# iv-12-tube-board-v2.net
KiCad netlist of a schematic drawn in EAGLE
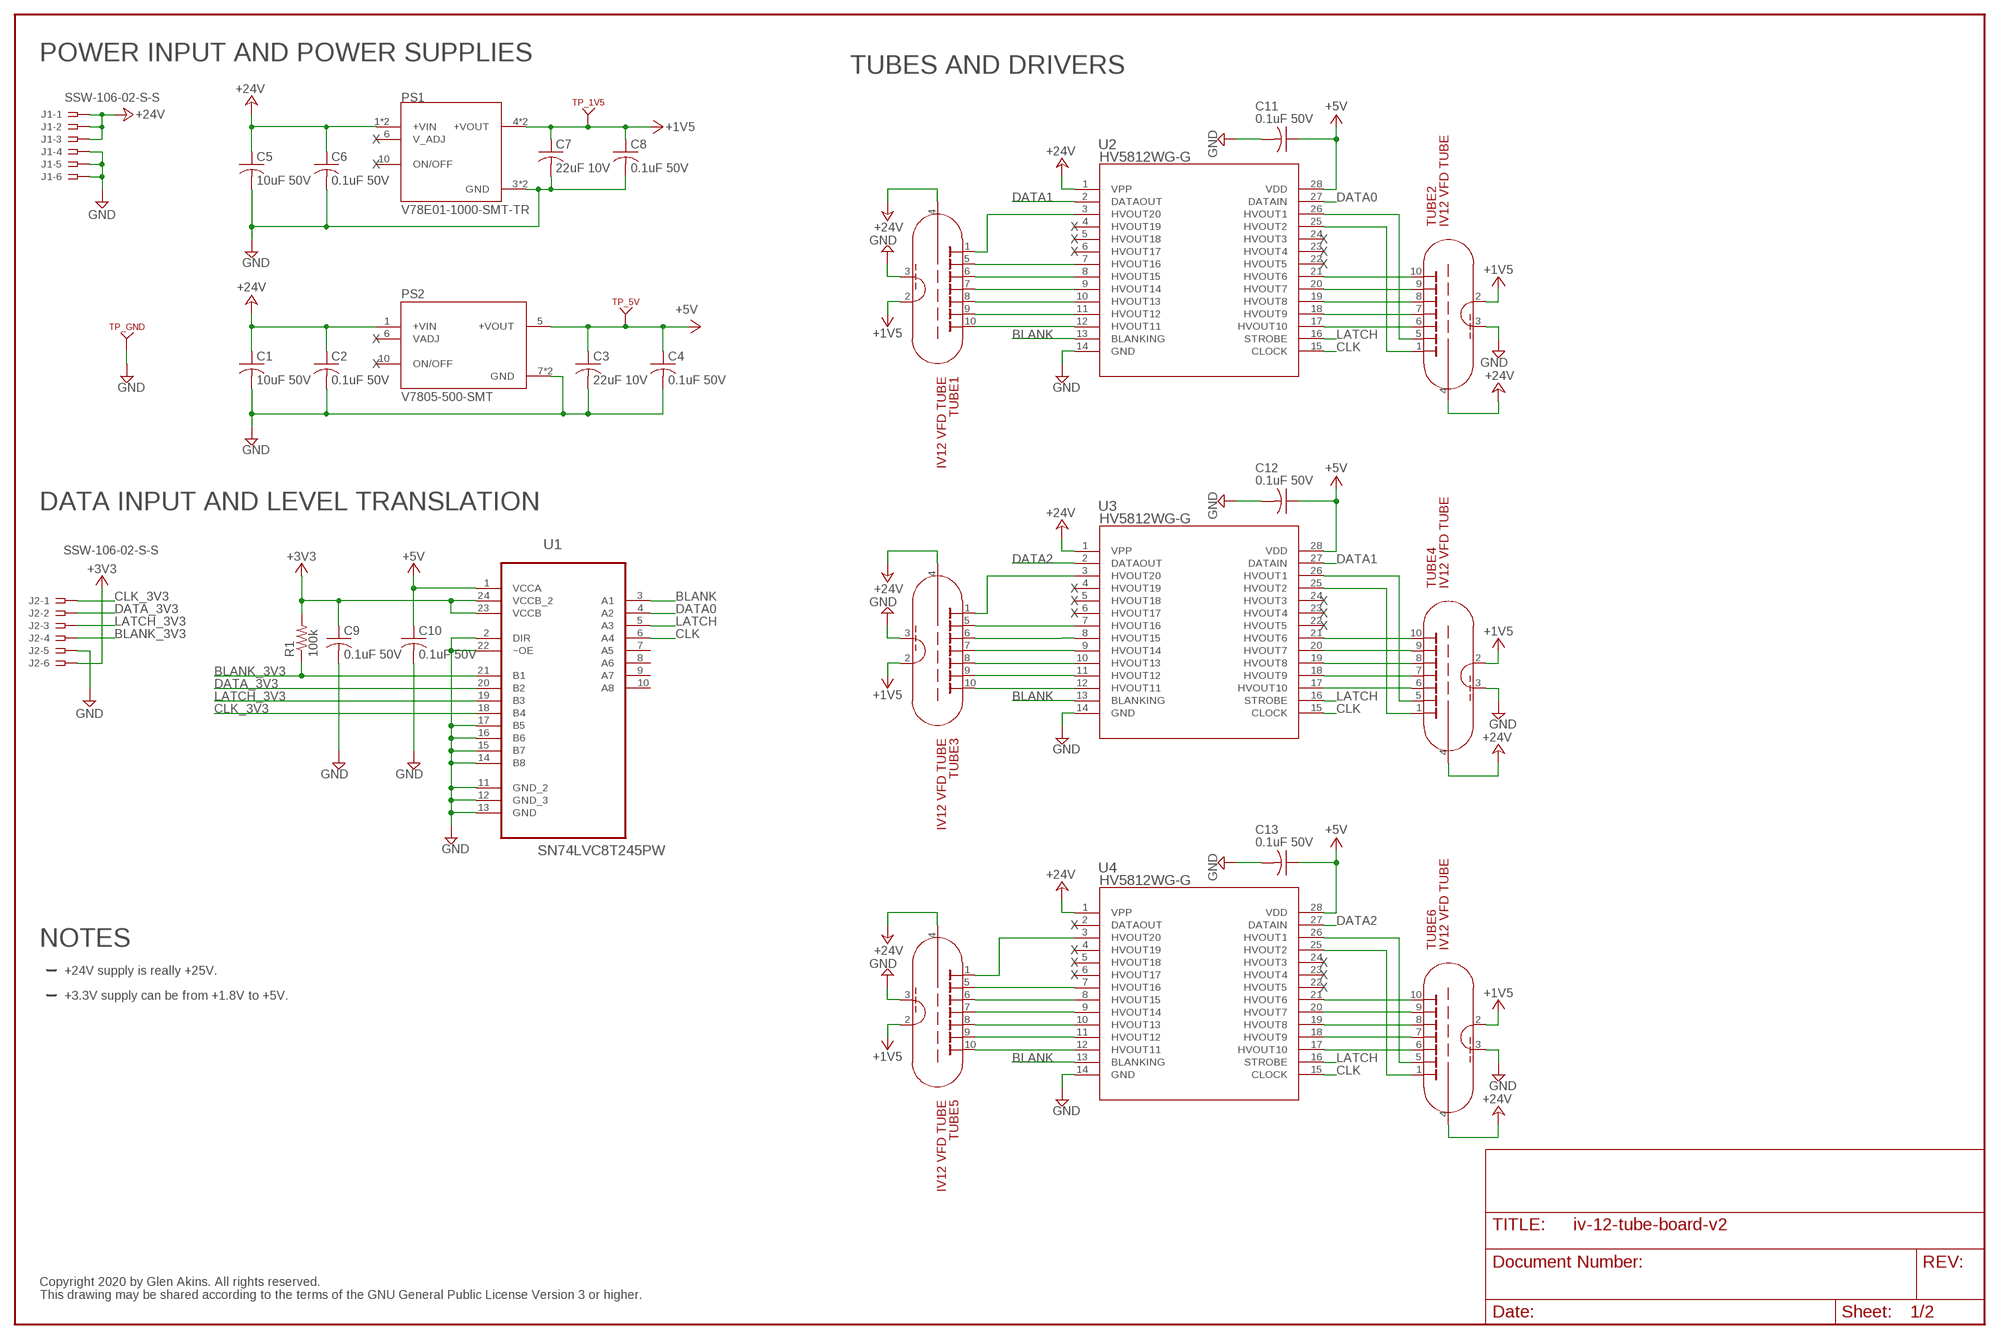
[diagram p0: schematic, sheet 1]
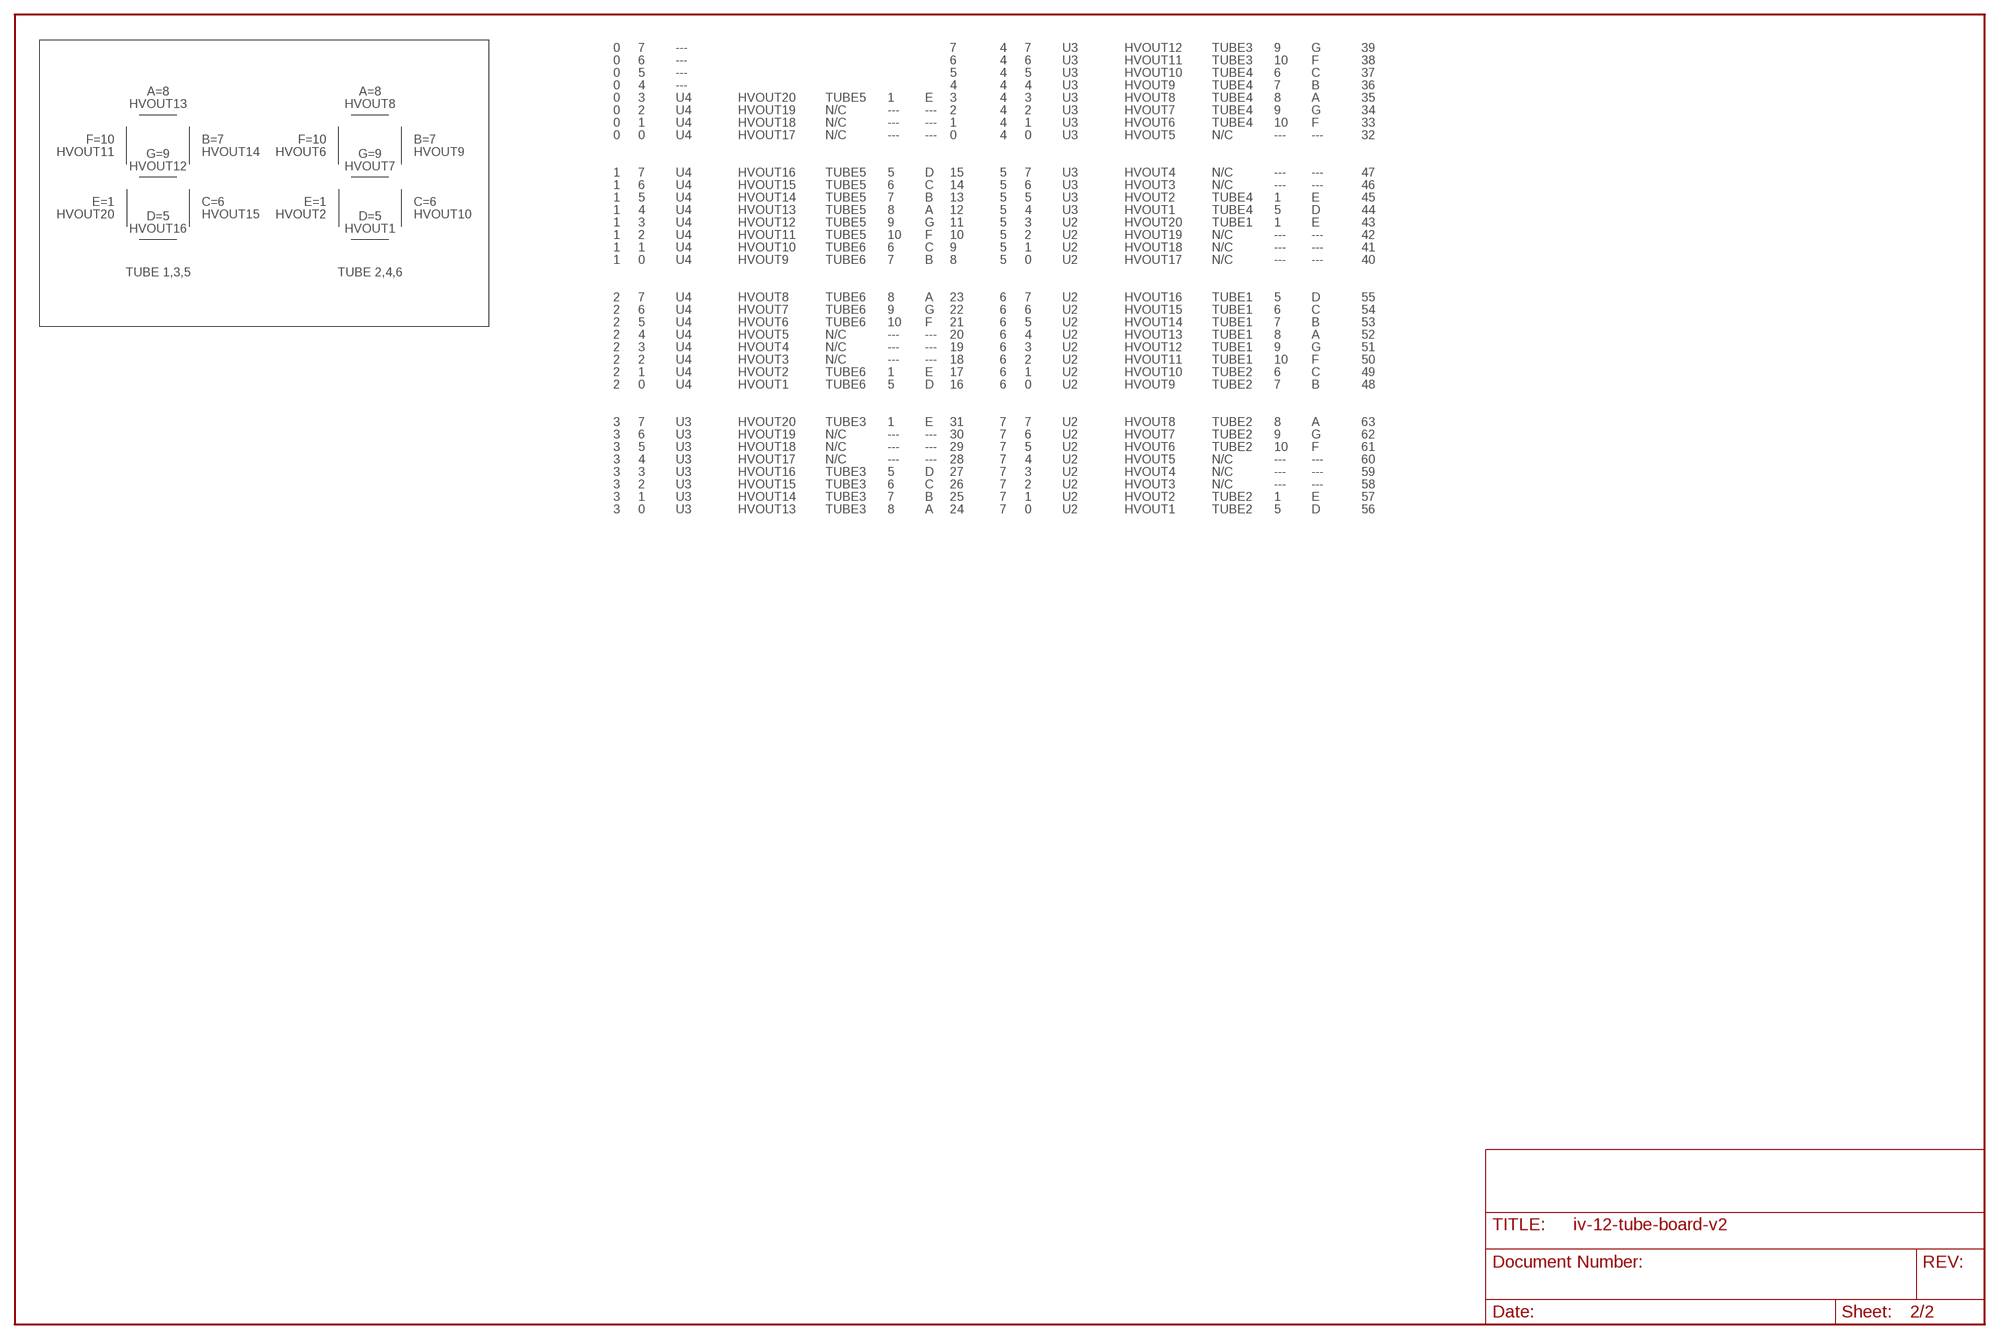
[diagram p1: schematic, sheet 2]

(export (version "E")
  (design (tool "Eeschema 10.0.6"))
  (components
    (comp (ref "C1")
      (value "10uF 50V")
      (footprint "eagle-import:C1210K")
      (fields (field (name "MFR") "KEMET") (field (name "MFR_PART_NO") "C1210C106K5RACTU"))
      (libsource (lib "eagle-import") (part "C-USC1210K"))
    )
    (comp (ref "C2")
      (value "0.1uF 50V")
      (footprint "eagle-import:C1206K")
      (fields (field (name "MFR") "KEMET") (field (name "MFR_PART_NO") "C1206S104M5RACTU"))
      (libsource (lib "eagle-import") (part "C-USC1206K"))
    )
    (comp (ref "C3")
      (value "22uF 10V")
      (footprint "eagle-import:C1206K")
      (fields (field (name "MFR") "KEMET") (field (name "MFR_PART_NO") "C1206C226K8RAC7800"))
      (libsource (lib "eagle-import") (part "C-USC1206K"))
    )
    (comp (ref "C4")
      (value "0.1uF 50V")
      (footprint "eagle-import:C1206K")
      (fields (field (name "MFR") "KEMET") (field (name "MFR_PART_NO") "C1206S104M5RACTU"))
      (libsource (lib "eagle-import") (part "C-USC1206K"))
    )
    (comp (ref "C5")
      (value "10uF 50V")
      (footprint "eagle-import:C1210K")
      (fields (field (name "MFR") "KEMET") (field (name "MFR_PART_NO") "C1210C106K5RACTU"))
      (libsource (lib "eagle-import") (part "C-USC1210K"))
    )
    (comp (ref "C6")
      (value "0.1uF 50V")
      (footprint "eagle-import:C1206K")
      (fields (field (name "MFR") "KEMET") (field (name "MFR_PART_NO") "C1206S104M5RACTU"))
      (libsource (lib "eagle-import") (part "C-USC1206K"))
    )
    (comp (ref "C7")
      (value "22uF 10V")
      (footprint "eagle-import:C1206K")
      (fields (field (name "MFR") "KEMET") (field (name "MFR_PART_NO") "C1206C226K8RAC7800"))
      (libsource (lib "eagle-import") (part "C-USC1206K"))
    )
    (comp (ref "C8")
      (value "0.1uF 50V")
      (footprint "eagle-import:C1206K")
      (fields (field (name "MFR") "KEMET") (field (name "MFR_PART_NO") "C1206S104M5RACTU"))
      (libsource (lib "eagle-import") (part "C-USC1206K"))
    )
    (comp (ref "C9")
      (value "0.1uF 50V")
      (footprint "eagle-import:C0805K")
      (libsource (lib "eagle-import") (part "C-USC0805K"))
    )
    (comp (ref "C10")
      (value "0.1uF 50V")
      (footprint "eagle-import:C0805K")
      (libsource (lib "eagle-import") (part "C-USC0805K"))
    )
    (comp (ref "C11")
      (value "0.1uF 50V")
      (footprint "eagle-import:C0805")
      (libsource (lib "eagle-import") (part "C-USC0805"))
    )
    (comp (ref "C12")
      (value "0.1uF 50V")
      (footprint "eagle-import:C0805")
      (libsource (lib "eagle-import") (part "C-USC0805"))
    )
    (comp (ref "C13")
      (value "0.1uF 50V")
      (footprint "eagle-import:C0805")
      (libsource (lib "eagle-import") (part "C-USC0805"))
    )
    (comp (ref "J1")
      (value "SSW-106-02-S-S")
      (footprint "eagle-import:SSW-106-02-S-S")
      (libsource (lib "eagle-import") (part "SSW-106-02-S-S"))
    )
    (comp (ref "J2")
      (value "SSW-106-02-S-S")
      (footprint "eagle-import:SSW-106-02-S-S")
      (libsource (lib "eagle-import") (part "SSW-106-02-S-S"))
    )
    (comp (ref "PS1")
      (value "V78E01-1000-SMT-TR")
      (footprint "eagle-import:CONV_V78E01-1000-SMT-TR")
      (fields (field (name "DIGI-KEY_PART_NUMBER") "102-5030-1-ND") (field (name "MF") "CUI Inc."))
      (libsource (lib "eagle-import") (part "V78E01-1000-SMT-TR"))
    )
    (comp (ref "PS2")
      (value "V7805-500-SMT")
      (footprint "eagle-import:CONV_V7805-500-SMT")
      (fields (field (name "MANUFACTURER") "CUI Inc"))
      (libsource (lib "eagle-import") (part "V7805-500-SMT"))
    )
    (comp (ref "R1")
      (value "100k")
      (footprint "eagle-import:R0805")
      (libsource (lib "eagle-import") (part "R-US_R0805"))
    )
    (comp (ref "TP_1V5")
      (value "KEYSTONE_500X")
      (footprint "eagle-import:KEYSTONE_TP500X")
      (libsource (lib "eagle-import") (part "KEYSTONE_500X"))
    )
    (comp (ref "TP_5V")
      (value "KEYSTONE_500X")
      (footprint "eagle-import:KEYSTONE_TP500X")
      (libsource (lib "eagle-import") (part "KEYSTONE_500X"))
    )
    (comp (ref "TP_GND")
      (value "KEYSTONE_500X")
      (footprint "eagle-import:KEYSTONE_TP500X")
      (libsource (lib "eagle-import") (part "KEYSTONE_500X"))
    )
    (comp (ref "TUBE1")
      (value "IV12 VFD TUBE")
      (footprint "eagle-import:IV-12-VFD-TUBE-11.9MM-10PIN-34DEG")
      (libsource (lib "eagle-import") (part "IV-12-VFD-TUBE"))
    )
    (comp (ref "TUBE2")
      (value "IV12 VFD TUBE")
      (footprint "eagle-import:IV-12-VFD-TUBE-11.9MM-10PIN-34DEG")
      (libsource (lib "eagle-import") (part "IV-12-VFD-TUBE"))
    )
    (comp (ref "TUBE3")
      (value "IV12 VFD TUBE")
      (footprint "eagle-import:IV-12-VFD-TUBE-11.9MM-10PIN-34DEG")
      (libsource (lib "eagle-import") (part "IV-12-VFD-TUBE"))
    )
    (comp (ref "TUBE4")
      (value "IV12 VFD TUBE")
      (footprint "eagle-import:IV-12-VFD-TUBE-11.9MM-10PIN-34DEG")
      (libsource (lib "eagle-import") (part "IV-12-VFD-TUBE"))
    )
    (comp (ref "TUBE5")
      (value "IV12 VFD TUBE")
      (footprint "eagle-import:IV-12-VFD-TUBE-11.9MM-10PIN-34DEG")
      (libsource (lib "eagle-import") (part "IV-12-VFD-TUBE"))
    )
    (comp (ref "TUBE6")
      (value "IV12 VFD TUBE")
      (footprint "eagle-import:IV-12-VFD-TUBE-11.9MM-10PIN-34DEG")
      (libsource (lib "eagle-import") (part "IV-12-VFD-TUBE"))
    )
    (comp (ref "U1")
      (value "SN74LVC8T245PW")
      (footprint "eagle-import:SOP65P640X120-24N")
      (fields (field (name "MPN") "SN74AVC8T245PW"))
      (libsource (lib "eagle-import") (part "SN74AVC8T245PW"))
    )
    (comp (ref "U2")
      (value "HV5812WG-G")
      (footprint "eagle-import:SOW28_17P90X7P50")
      (fields (field (name "COPYRIGHT") "Copyright (C) 2018 Accelerated Designs. All rights reserved"))
      (libsource (lib "eagle-import") (part "HV5812WG-G"))
    )
    (comp (ref "U3")
      (value "HV5812WG-G")
      (footprint "eagle-import:SOW28_17P90X7P50")
      (fields (field (name "COPYRIGHT") "Copyright (C) 2018 Accelerated Designs. All rights reserved"))
      (libsource (lib "eagle-import") (part "HV5812WG-G"))
    )
    (comp (ref "U4")
      (value "HV5812WG-G")
      (footprint "eagle-import:SOW28_17P90X7P50")
      (fields (field (name "COPYRIGHT") "Copyright (C) 2018 Accelerated Designs. All rights reserved"))
      (libsource (lib "eagle-import") (part "HV5812WG-G"))
    )
  )
  (nets
    (net (code "1") (name "+1V5") (class "Default")
      (node (ref "C7") (pin "1") (pinfunction "1_1") (pintype "passive"))
      (node (ref "C8") (pin "1") (pinfunction "1_1") (pintype "passive"))
      (node (ref "PS1") (pin "4") (pinfunction "+VOUT_4") (pintype "output"))
      (node (ref "PS1") (pin "5") (pinfunction "+VOUT_5") (pintype "output"))
      (node (ref "TP_1V5") (pin "1") (pinfunction "P$1_1") (pintype "bidirectional"))
      (node (ref "TUBE1") (pin "2") (pinfunction "2_2") (pintype "bidirectional"))
      (node (ref "TUBE2") (pin "2") (pinfunction "2_2") (pintype "bidirectional"))
      (node (ref "TUBE3") (pin "2") (pinfunction "2_2") (pintype "bidirectional"))
      (node (ref "TUBE4") (pin "2") (pinfunction "2_2") (pintype "bidirectional"))
      (node (ref "TUBE5") (pin "2") (pinfunction "2_2") (pintype "bidirectional"))
      (node (ref "TUBE6") (pin "2") (pinfunction "2_2") (pintype "bidirectional"))
    )
    (net (code "2") (name "+3V3") (class "Default")
      (node (ref "C9") (pin "1") (pinfunction "1_1") (pintype "passive"))
      (node (ref "J2") (pin "6") (pinfunction "1_6") (pintype "passive"))
      (node (ref "R1") (pin "2") (pinfunction "2_2") (pintype "passive"))
      (node (ref "U1") (pin "23") (pinfunction "VCCB_23") (pintype "power_in"))
      (node (ref "U1") (pin "24") (pinfunction "VCCB_2_24") (pintype "power_in"))
    )
    (net (code "3") (name "+5V") (class "Default")
      (node (ref "C10") (pin "1") (pinfunction "1_1") (pintype "passive"))
      (node (ref "C11") (pin "1") (pinfunction "1_1") (pintype "passive"))
      (node (ref "C12") (pin "1") (pinfunction "1_1") (pintype "passive"))
      (node (ref "C13") (pin "1") (pinfunction "1_1") (pintype "passive"))
      (node (ref "C3") (pin "1") (pinfunction "1_1") (pintype "passive"))
      (node (ref "C4") (pin "1") (pinfunction "1_1") (pintype "passive"))
      (node (ref "PS2") (pin "5") (pinfunction "+VOUT_5") (pintype "output"))
      (node (ref "TP_5V") (pin "1") (pinfunction "P$1_1") (pintype "bidirectional"))
      (node (ref "U1") (pin "1") (pinfunction "VCCA_1") (pintype "power_in"))
      (node (ref "U2") (pin "28") (pinfunction "VDD_28") (pintype "power_in"))
      (node (ref "U3") (pin "28") (pinfunction "VDD_28") (pintype "power_in"))
      (node (ref "U4") (pin "28") (pinfunction "VDD_28") (pintype "power_in"))
    )
    (net (code "4") (name "+24V") (class "Default")
      (node (ref "C1") (pin "1") (pinfunction "1_1") (pintype "passive"))
      (node (ref "C2") (pin "1") (pinfunction "1_1") (pintype "passive"))
      (node (ref "C5") (pin "1") (pinfunction "1_1") (pintype "passive"))
      (node (ref "C6") (pin "1") (pinfunction "1_1") (pintype "passive"))
      (node (ref "J1") (pin "1") (pinfunction "1_1") (pintype "passive"))
      (node (ref "J1") (pin "2") (pinfunction "1_2") (pintype "passive"))
      (node (ref "J1") (pin "3") (pinfunction "1_3") (pintype "passive"))
      (node (ref "PS1") (pin "1") (pinfunction "+VIN_1") (pintype "input"))
      (node (ref "PS1") (pin "2") (pinfunction "+VIN_2") (pintype "input"))
      (node (ref "PS2") (pin "1") (pinfunction "+VIN_1") (pintype "input"))
      (node (ref "TUBE1") (pin "4") (pinfunction "4_4") (pintype "bidirectional"))
      (node (ref "TUBE2") (pin "4") (pinfunction "4_4") (pintype "bidirectional"))
      (node (ref "TUBE3") (pin "4") (pinfunction "4_4") (pintype "bidirectional"))
      (node (ref "TUBE4") (pin "4") (pinfunction "4_4") (pintype "bidirectional"))
      (node (ref "TUBE5") (pin "4") (pinfunction "4_4") (pintype "bidirectional"))
      (node (ref "TUBE6") (pin "4") (pinfunction "4_4") (pintype "bidirectional"))
      (node (ref "U2") (pin "1") (pinfunction "VPP_1") (pintype "power_in"))
      (node (ref "U3") (pin "1") (pinfunction "VPP_1") (pintype "power_in"))
      (node (ref "U4") (pin "1") (pinfunction "VPP_1") (pintype "power_in"))
    )
    (net (code "5") (name "BLANK") (class "Default")
      (node (ref "U1") (pin "3") (pinfunction "A1_3") (pintype "bidirectional"))
      (node (ref "U2") (pin "13") (pinfunction "BLANKING_13") (pintype "passive"))
      (node (ref "U3") (pin "13") (pinfunction "BLANKING_13") (pintype "passive"))
      (node (ref "U4") (pin "13") (pinfunction "BLANKING_13") (pintype "passive"))
    )
    (net (code "6") (name "BLANK_3V3") (class "Default")
      (node (ref "J2") (pin "4") (pinfunction "1_4") (pintype "passive"))
      (node (ref "R1") (pin "1") (pinfunction "1_1") (pintype "passive"))
      (node (ref "U1") (pin "21") (pinfunction "B1_21") (pintype "bidirectional"))
    )
    (net (code "7") (name "CLK") (class "Default")
      (node (ref "U1") (pin "6") (pinfunction "A4_6") (pintype "bidirectional"))
      (node (ref "U2") (pin "15") (pinfunction "CLOCK_15") (pintype "passive"))
      (node (ref "U3") (pin "15") (pinfunction "CLOCK_15") (pintype "passive"))
      (node (ref "U4") (pin "15") (pinfunction "CLOCK_15") (pintype "passive"))
    )
    (net (code "8") (name "CLK_3V3") (class "Default")
      (node (ref "J2") (pin "1") (pinfunction "1_1") (pintype "passive"))
      (node (ref "U1") (pin "18") (pinfunction "B4_18") (pintype "bidirectional"))
    )
    (net (code "9") (name "DATA0") (class "Default")
      (node (ref "U1") (pin "4") (pinfunction "A2_4") (pintype "bidirectional"))
      (node (ref "U2") (pin "27") (pinfunction "DATAIN_27") (pintype "input"))
    )
    (net (code "10") (name "DATA1") (class "Default")
      (node (ref "U2") (pin "2") (pinfunction "DATAOUT_2") (pintype "output"))
      (node (ref "U3") (pin "27") (pinfunction "DATAIN_27") (pintype "input"))
    )
    (net (code "11") (name "DATA2") (class "Default")
      (node (ref "U3") (pin "2") (pinfunction "DATAOUT_2") (pintype "output"))
      (node (ref "U4") (pin "27") (pinfunction "DATAIN_27") (pintype "input"))
    )
    (net (code "12") (name "DATA_3V3") (class "Default")
      (node (ref "J2") (pin "2") (pinfunction "1_2") (pintype "passive"))
      (node (ref "U1") (pin "20") (pinfunction "B2_20") (pintype "bidirectional"))
    )
    (net (code "13") (name "GND") (class "Default")
      (node (ref "C1") (pin "2") (pinfunction "2_2") (pintype "passive"))
      (node (ref "C10") (pin "2") (pinfunction "2_2") (pintype "passive"))
      (node (ref "C11") (pin "2") (pinfunction "2_2") (pintype "passive"))
      (node (ref "C12") (pin "2") (pinfunction "2_2") (pintype "passive"))
      (node (ref "C13") (pin "2") (pinfunction "2_2") (pintype "passive"))
      (node (ref "C2") (pin "2") (pinfunction "2_2") (pintype "passive"))
      (node (ref "C3") (pin "2") (pinfunction "2_2") (pintype "passive"))
      (node (ref "C4") (pin "2") (pinfunction "2_2") (pintype "passive"))
      (node (ref "C5") (pin "2") (pinfunction "2_2") (pintype "passive"))
      (node (ref "C6") (pin "2") (pinfunction "2_2") (pintype "passive"))
      (node (ref "C7") (pin "2") (pinfunction "2_2") (pintype "passive"))
      (node (ref "C8") (pin "2") (pinfunction "2_2") (pintype "passive"))
      (node (ref "C9") (pin "2") (pinfunction "2_2") (pintype "passive"))
      (node (ref "J1") (pin "4") (pinfunction "1_4") (pintype "passive"))
      (node (ref "J1") (pin "5") (pinfunction "1_5") (pintype "passive"))
      (node (ref "J1") (pin "6") (pinfunction "1_6") (pintype "passive"))
      (node (ref "J2") (pin "5") (pinfunction "1_5") (pintype "passive"))
      (node (ref "PS1") (pin "3") (pinfunction "GND_3") (pintype "power_in"))
      (node (ref "PS1") (pin "7") (pinfunction "GND_7") (pintype "power_in"))
      (node (ref "PS2") (pin "7") (pinfunction "GND_7") (pintype "power_in"))
      (node (ref "PS2") (pin "9") (pinfunction "GND_9") (pintype "power_in"))
      (node (ref "TP_GND") (pin "1") (pinfunction "P$1_1") (pintype "bidirectional"))
      (node (ref "TUBE1") (pin "3") (pinfunction "3_3") (pintype "bidirectional"))
      (node (ref "TUBE2") (pin "3") (pinfunction "3_3") (pintype "bidirectional"))
      (node (ref "TUBE3") (pin "3") (pinfunction "3_3") (pintype "bidirectional"))
      (node (ref "TUBE4") (pin "3") (pinfunction "3_3") (pintype "bidirectional"))
      (node (ref "TUBE5") (pin "3") (pinfunction "3_3") (pintype "bidirectional"))
      (node (ref "TUBE6") (pin "3") (pinfunction "3_3") (pintype "bidirectional"))
      (node (ref "U1") (pin "11") (pinfunction "GND_2_11") (pintype "passive"))
      (node (ref "U1") (pin "12") (pinfunction "GND_3_12") (pintype "passive"))
      (node (ref "U1") (pin "13") (pinfunction "GND_13") (pintype "passive"))
      (node (ref "U1") (pin "14") (pinfunction "B8_14") (pintype "bidirectional"))
      (node (ref "U1") (pin "15") (pinfunction "B7_15") (pintype "bidirectional"))
      (node (ref "U1") (pin "16") (pinfunction "B6_16") (pintype "bidirectional"))
      (node (ref "U1") (pin "17") (pinfunction "B5_17") (pintype "bidirectional"))
      (node (ref "U1") (pin "2") (pinfunction "DIR_2") (pintype "input"))
      (node (ref "U1") (pin "22") (pinfunction "~{OE}_22") (pintype "input"))
      (node (ref "U2") (pin "14") (pinfunction "GND_14") (pintype "passive"))
      (node (ref "U3") (pin "14") (pinfunction "GND_14") (pintype "passive"))
      (node (ref "U4") (pin "14") (pinfunction "GND_14") (pintype "passive"))
    )
    (net (code "14") (name "LATCH") (class "Default")
      (node (ref "U1") (pin "5") (pinfunction "A3_5") (pintype "bidirectional"))
      (node (ref "U2") (pin "16") (pinfunction "STROBE_16") (pintype "passive"))
      (node (ref "U3") (pin "16") (pinfunction "STROBE_16") (pintype "passive"))
      (node (ref "U4") (pin "16") (pinfunction "STROBE_16") (pintype "passive"))
    )
    (net (code "15") (name "LATCH_3V3") (class "Default")
      (node (ref "J2") (pin "3") (pinfunction "1_3") (pintype "passive"))
      (node (ref "U1") (pin "19") (pinfunction "B3_19") (pintype "bidirectional"))
    )
    (net (code "16") (name "Net-(U2-HVOUT1)") (class "Default")
      (node (ref "TUBE2") (pin "5") (pinfunction "5_5") (pintype "bidirectional"))
      (node (ref "U2") (pin "26") (pinfunction "HVOUT1_26") (pintype "output"))
    )
    (net (code "17") (name "Net-(U2-HVOUT2)") (class "Default")
      (node (ref "TUBE2") (pin "1") (pinfunction "1_1") (pintype "bidirectional"))
      (node (ref "U2") (pin "25") (pinfunction "HVOUT2_25") (pintype "output"))
    )
    (net (code "18") (name "Net-(U2-HVOUT6)") (class "Default")
      (node (ref "TUBE2") (pin "10") (pinfunction "10_10") (pintype "bidirectional"))
      (node (ref "U2") (pin "21") (pinfunction "HVOUT6_21") (pintype "output"))
    )
    (net (code "19") (name "Net-(U2-HVOUT7)") (class "Default")
      (node (ref "TUBE2") (pin "9") (pinfunction "9_9") (pintype "bidirectional"))
      (node (ref "U2") (pin "20") (pinfunction "HVOUT7_20") (pintype "output"))
    )
    (net (code "20") (name "Net-(U2-HVOUT8)") (class "Default")
      (node (ref "TUBE2") (pin "8") (pinfunction "8_8") (pintype "bidirectional"))
      (node (ref "U2") (pin "19") (pinfunction "HVOUT8_19") (pintype "output"))
    )
    (net (code "21") (name "Net-(U2-HVOUT9)") (class "Default")
      (node (ref "TUBE2") (pin "7") (pinfunction "7_7") (pintype "bidirectional"))
      (node (ref "U2") (pin "18") (pinfunction "HVOUT9_18") (pintype "output"))
    )
    (net (code "22") (name "Net-(U2-HVOUT10)") (class "Default")
      (node (ref "TUBE2") (pin "6") (pinfunction "6_6") (pintype "bidirectional"))
      (node (ref "U2") (pin "17") (pinfunction "HVOUT10_17") (pintype "output"))
    )
    (net (code "23") (name "Net-(U2-HVOUT11)") (class "Default")
      (node (ref "TUBE1") (pin "10") (pinfunction "10_10") (pintype "bidirectional"))
      (node (ref "U2") (pin "12") (pinfunction "HVOUT11_12") (pintype "output"))
    )
    (net (code "24") (name "Net-(U2-HVOUT12)") (class "Default")
      (node (ref "TUBE1") (pin "9") (pinfunction "9_9") (pintype "bidirectional"))
      (node (ref "U2") (pin "11") (pinfunction "HVOUT12_11") (pintype "output"))
    )
    (net (code "25") (name "Net-(U2-HVOUT13)") (class "Default")
      (node (ref "TUBE1") (pin "8") (pinfunction "8_8") (pintype "bidirectional"))
      (node (ref "U2") (pin "10") (pinfunction "HVOUT13_10") (pintype "output"))
    )
    (net (code "26") (name "Net-(U2-HVOUT14)") (class "Default")
      (node (ref "TUBE1") (pin "7") (pinfunction "7_7") (pintype "bidirectional"))
      (node (ref "U2") (pin "9") (pinfunction "HVOUT14_9") (pintype "output"))
    )
    (net (code "27") (name "Net-(U2-HVOUT15)") (class "Default")
      (node (ref "TUBE1") (pin "6") (pinfunction "6_6") (pintype "bidirectional"))
      (node (ref "U2") (pin "8") (pinfunction "HVOUT15_8") (pintype "output"))
    )
    (net (code "28") (name "Net-(U2-HVOUT16)") (class "Default")
      (node (ref "TUBE1") (pin "5") (pinfunction "5_5") (pintype "bidirectional"))
      (node (ref "U2") (pin "7") (pinfunction "HVOUT16_7") (pintype "output"))
    )
    (net (code "29") (name "Net-(U2-HVOUT20)") (class "Default")
      (node (ref "TUBE1") (pin "1") (pinfunction "1_1") (pintype "bidirectional"))
      (node (ref "U2") (pin "3") (pinfunction "HVOUT20_3") (pintype "output"))
    )
    (net (code "30") (name "Net-(U3-HVOUT1)") (class "Default")
      (node (ref "TUBE4") (pin "5") (pinfunction "5_5") (pintype "bidirectional"))
      (node (ref "U3") (pin "26") (pinfunction "HVOUT1_26") (pintype "output"))
    )
    (net (code "31") (name "Net-(U3-HVOUT2)") (class "Default")
      (node (ref "TUBE4") (pin "1") (pinfunction "1_1") (pintype "bidirectional"))
      (node (ref "U3") (pin "25") (pinfunction "HVOUT2_25") (pintype "output"))
    )
    (net (code "32") (name "Net-(U3-HVOUT6)") (class "Default")
      (node (ref "TUBE4") (pin "10") (pinfunction "10_10") (pintype "bidirectional"))
      (node (ref "U3") (pin "21") (pinfunction "HVOUT6_21") (pintype "output"))
    )
    (net (code "33") (name "Net-(U3-HVOUT7)") (class "Default")
      (node (ref "TUBE4") (pin "9") (pinfunction "9_9") (pintype "bidirectional"))
      (node (ref "U3") (pin "20") (pinfunction "HVOUT7_20") (pintype "output"))
    )
    (net (code "34") (name "Net-(U3-HVOUT8)") (class "Default")
      (node (ref "TUBE4") (pin "8") (pinfunction "8_8") (pintype "bidirectional"))
      (node (ref "U3") (pin "19") (pinfunction "HVOUT8_19") (pintype "output"))
    )
    (net (code "35") (name "Net-(U3-HVOUT9)") (class "Default")
      (node (ref "TUBE4") (pin "7") (pinfunction "7_7") (pintype "bidirectional"))
      (node (ref "U3") (pin "18") (pinfunction "HVOUT9_18") (pintype "output"))
    )
    (net (code "36") (name "Net-(U3-HVOUT10)") (class "Default")
      (node (ref "TUBE4") (pin "6") (pinfunction "6_6") (pintype "bidirectional"))
      (node (ref "U3") (pin "17") (pinfunction "HVOUT10_17") (pintype "output"))
    )
    (net (code "37") (name "Net-(U3-HVOUT11)") (class "Default")
      (node (ref "TUBE3") (pin "10") (pinfunction "10_10") (pintype "bidirectional"))
      (node (ref "U3") (pin "12") (pinfunction "HVOUT11_12") (pintype "output"))
    )
    (net (code "38") (name "Net-(U3-HVOUT12)") (class "Default")
      (node (ref "TUBE3") (pin "9") (pinfunction "9_9") (pintype "bidirectional"))
      (node (ref "U3") (pin "11") (pinfunction "HVOUT12_11") (pintype "output"))
    )
    (net (code "39") (name "Net-(U3-HVOUT13)") (class "Default")
      (node (ref "TUBE3") (pin "8") (pinfunction "8_8") (pintype "bidirectional"))
      (node (ref "U3") (pin "10") (pinfunction "HVOUT13_10") (pintype "output"))
    )
    (net (code "40") (name "Net-(U3-HVOUT14)") (class "Default")
      (node (ref "TUBE3") (pin "7") (pinfunction "7_7") (pintype "bidirectional"))
      (node (ref "U3") (pin "9") (pinfunction "HVOUT14_9") (pintype "output"))
    )
    (net (code "41") (name "Net-(U3-HVOUT15)") (class "Default")
      (node (ref "TUBE3") (pin "6") (pinfunction "6_6") (pintype "bidirectional"))
      (node (ref "U3") (pin "8") (pinfunction "HVOUT15_8") (pintype "output"))
    )
    (net (code "42") (name "Net-(U3-HVOUT16)") (class "Default")
      (node (ref "TUBE3") (pin "5") (pinfunction "5_5") (pintype "bidirectional"))
      (node (ref "U3") (pin "7") (pinfunction "HVOUT16_7") (pintype "output"))
    )
    (net (code "43") (name "Net-(U3-HVOUT20)") (class "Default")
      (node (ref "TUBE3") (pin "1") (pinfunction "1_1") (pintype "bidirectional"))
      (node (ref "U3") (pin "3") (pinfunction "HVOUT20_3") (pintype "output"))
    )
    (net (code "44") (name "Net-(U4-HVOUT1)") (class "Default")
      (node (ref "TUBE6") (pin "5") (pinfunction "5_5") (pintype "bidirectional"))
      (node (ref "U4") (pin "26") (pinfunction "HVOUT1_26") (pintype "output"))
    )
    (net (code "45") (name "Net-(U4-HVOUT2)") (class "Default")
      (node (ref "TUBE6") (pin "1") (pinfunction "1_1") (pintype "bidirectional"))
      (node (ref "U4") (pin "25") (pinfunction "HVOUT2_25") (pintype "output"))
    )
    (net (code "46") (name "Net-(U4-HVOUT6)") (class "Default")
      (node (ref "TUBE6") (pin "10") (pinfunction "10_10") (pintype "bidirectional"))
      (node (ref "U4") (pin "21") (pinfunction "HVOUT6_21") (pintype "output"))
    )
    (net (code "47") (name "Net-(U4-HVOUT7)") (class "Default")
      (node (ref "TUBE6") (pin "9") (pinfunction "9_9") (pintype "bidirectional"))
      (node (ref "U4") (pin "20") (pinfunction "HVOUT7_20") (pintype "output"))
    )
    (net (code "48") (name "Net-(U4-HVOUT8)") (class "Default")
      (node (ref "TUBE6") (pin "8") (pinfunction "8_8") (pintype "bidirectional"))
      (node (ref "U4") (pin "19") (pinfunction "HVOUT8_19") (pintype "output"))
    )
    (net (code "49") (name "Net-(U4-HVOUT9)") (class "Default")
      (node (ref "TUBE6") (pin "7") (pinfunction "7_7") (pintype "bidirectional"))
      (node (ref "U4") (pin "18") (pinfunction "HVOUT9_18") (pintype "output"))
    )
    (net (code "50") (name "Net-(U4-HVOUT10)") (class "Default")
      (node (ref "TUBE6") (pin "6") (pinfunction "6_6") (pintype "bidirectional"))
      (node (ref "U4") (pin "17") (pinfunction "HVOUT10_17") (pintype "output"))
    )
    (net (code "51") (name "Net-(U4-HVOUT11)") (class "Default")
      (node (ref "TUBE5") (pin "10") (pinfunction "10_10") (pintype "bidirectional"))
      (node (ref "U4") (pin "12") (pinfunction "HVOUT11_12") (pintype "output"))
    )
    (net (code "52") (name "Net-(U4-HVOUT12)") (class "Default")
      (node (ref "TUBE5") (pin "9") (pinfunction "9_9") (pintype "bidirectional"))
      (node (ref "U4") (pin "11") (pinfunction "HVOUT12_11") (pintype "output"))
    )
    (net (code "53") (name "Net-(U4-HVOUT13)") (class "Default")
      (node (ref "TUBE5") (pin "8") (pinfunction "8_8") (pintype "bidirectional"))
      (node (ref "U4") (pin "10") (pinfunction "HVOUT13_10") (pintype "output"))
    )
    (net (code "54") (name "Net-(U4-HVOUT14)") (class "Default")
      (node (ref "TUBE5") (pin "7") (pinfunction "7_7") (pintype "bidirectional"))
      (node (ref "U4") (pin "9") (pinfunction "HVOUT14_9") (pintype "output"))
    )
    (net (code "55") (name "Net-(U4-HVOUT15)") (class "Default")
      (node (ref "TUBE5") (pin "6") (pinfunction "6_6") (pintype "bidirectional"))
      (node (ref "U4") (pin "8") (pinfunction "HVOUT15_8") (pintype "output"))
    )
    (net (code "56") (name "Net-(U4-HVOUT16)") (class "Default")
      (node (ref "TUBE5") (pin "5") (pinfunction "5_5") (pintype "bidirectional"))
      (node (ref "U4") (pin "7") (pinfunction "HVOUT16_7") (pintype "output"))
    )
    (net (code "57") (name "Net-(U4-HVOUT20)") (class "Default")
      (node (ref "TUBE5") (pin "1") (pinfunction "1_1") (pintype "bidirectional"))
      (node (ref "U4") (pin "3") (pinfunction "HVOUT20_3") (pintype "output"))
    )
    (net (code "58") (name "unconnected-(PS1-ON{slash}OFF-Pad10)") (class "Default")
      (node (ref "PS1") (pin "10") (pinfunction "ON/OFF_10") (pintype "input"))
    )
    (net (code "59") (name "unconnected-(PS1-V_ADJ-Pad6)") (class "Default")
      (node (ref "PS1") (pin "6") (pinfunction "V_ADJ_6") (pintype "input"))
    )
    (net (code "60") (name "unconnected-(PS2-ON{slash}OFF-Pad10)") (class "Default")
      (node (ref "PS2") (pin "10") (pinfunction "ON/OFF_10") (pintype "input"))
    )
    (net (code "61") (name "unconnected-(PS2-VADJ-Pad6)") (class "Default")
      (node (ref "PS2") (pin "6") (pinfunction "VADJ_6") (pintype "input"))
    )
    (net (code "62") (name "unconnected-(U1-A5-Pad7)") (class "Default")
      (node (ref "U1") (pin "7") (pinfunction "A5_7") (pintype "bidirectional"))
    )
    (net (code "63") (name "unconnected-(U1-A6-Pad8)") (class "Default")
      (node (ref "U1") (pin "8") (pinfunction "A6_8") (pintype "bidirectional"))
    )
    (net (code "64") (name "unconnected-(U1-A7-Pad9)") (class "Default")
      (node (ref "U1") (pin "9") (pinfunction "A7_9") (pintype "bidirectional"))
    )
    (net (code "65") (name "unconnected-(U1-A8-Pad10)") (class "Default")
      (node (ref "U1") (pin "10") (pinfunction "A8_10") (pintype "bidirectional"))
    )
    (net (code "66") (name "unconnected-(U2-HVOUT3-Pad24)") (class "Default")
      (node (ref "U2") (pin "24") (pinfunction "HVOUT3_24") (pintype "output"))
    )
    (net (code "67") (name "unconnected-(U2-HVOUT4-Pad23)") (class "Default")
      (node (ref "U2") (pin "23") (pinfunction "HVOUT4_23") (pintype "output"))
    )
    (net (code "68") (name "unconnected-(U2-HVOUT5-Pad22)") (class "Default")
      (node (ref "U2") (pin "22") (pinfunction "HVOUT5_22") (pintype "output"))
    )
    (net (code "69") (name "unconnected-(U2-HVOUT17-Pad6)") (class "Default")
      (node (ref "U2") (pin "6") (pinfunction "HVOUT17_6") (pintype "output"))
    )
    (net (code "70") (name "unconnected-(U2-HVOUT18-Pad5)") (class "Default")
      (node (ref "U2") (pin "5") (pinfunction "HVOUT18_5") (pintype "output"))
    )
    (net (code "71") (name "unconnected-(U2-HVOUT19-Pad4)") (class "Default")
      (node (ref "U2") (pin "4") (pinfunction "HVOUT19_4") (pintype "output"))
    )
    (net (code "72") (name "unconnected-(U3-HVOUT3-Pad24)") (class "Default")
      (node (ref "U3") (pin "24") (pinfunction "HVOUT3_24") (pintype "output"))
    )
    (net (code "73") (name "unconnected-(U3-HVOUT4-Pad23)") (class "Default")
      (node (ref "U3") (pin "23") (pinfunction "HVOUT4_23") (pintype "output"))
    )
    (net (code "74") (name "unconnected-(U3-HVOUT5-Pad22)") (class "Default")
      (node (ref "U3") (pin "22") (pinfunction "HVOUT5_22") (pintype "output"))
    )
    (net (code "75") (name "unconnected-(U3-HVOUT17-Pad6)") (class "Default")
      (node (ref "U3") (pin "6") (pinfunction "HVOUT17_6") (pintype "output"))
    )
    (net (code "76") (name "unconnected-(U3-HVOUT18-Pad5)") (class "Default")
      (node (ref "U3") (pin "5") (pinfunction "HVOUT18_5") (pintype "output"))
    )
    (net (code "77") (name "unconnected-(U3-HVOUT19-Pad4)") (class "Default")
      (node (ref "U3") (pin "4") (pinfunction "HVOUT19_4") (pintype "output"))
    )
    (net (code "78") (name "unconnected-(U4-DATAOUT-Pad2)") (class "Default")
      (node (ref "U4") (pin "2") (pinfunction "DATAOUT_2") (pintype "output"))
    )
    (net (code "79") (name "unconnected-(U4-HVOUT3-Pad24)") (class "Default")
      (node (ref "U4") (pin "24") (pinfunction "HVOUT3_24") (pintype "output"))
    )
    (net (code "80") (name "unconnected-(U4-HVOUT4-Pad23)") (class "Default")
      (node (ref "U4") (pin "23") (pinfunction "HVOUT4_23") (pintype "output"))
    )
    (net (code "81") (name "unconnected-(U4-HVOUT5-Pad22)") (class "Default")
      (node (ref "U4") (pin "22") (pinfunction "HVOUT5_22") (pintype "output"))
    )
    (net (code "82") (name "unconnected-(U4-HVOUT17-Pad6)") (class "Default")
      (node (ref "U4") (pin "6") (pinfunction "HVOUT17_6") (pintype "output"))
    )
    (net (code "83") (name "unconnected-(U4-HVOUT18-Pad5)") (class "Default")
      (node (ref "U4") (pin "5") (pinfunction "HVOUT18_5") (pintype "output"))
    )
    (net (code "84") (name "unconnected-(U4-HVOUT19-Pad4)") (class "Default")
      (node (ref "U4") (pin "4") (pinfunction "HVOUT19_4") (pintype "output"))
    )
  )
)
